# Thermokoppel.net
KiCad netlist of a schematic drawn in Altium Designer
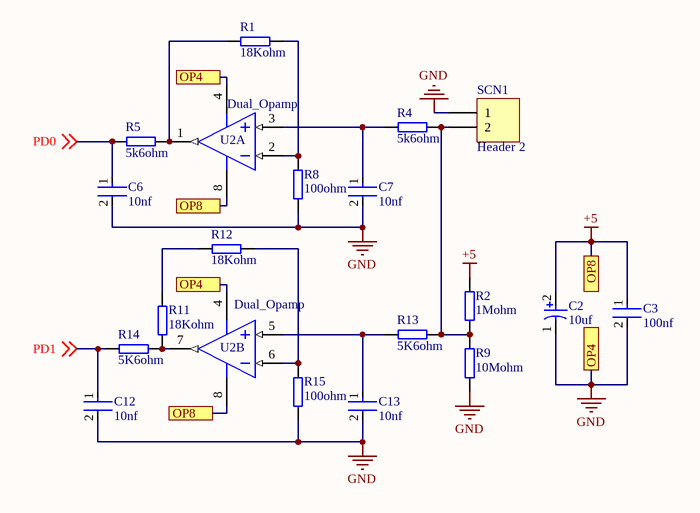
[diagram p0: Thermokoppel.SchDoc]

(export (version "E")
  (design (tool "Eeschema 10.0.6"))
  (components
    (comp (ref "C2")
      (value "10uf")
      (footprint "CE_D4_L5,4")
      (fields (field (name "MANUFACTURER") "Panasonic"))
      (libsource (lib "Soldeerstation_Final") (part "Capacitor_Electrolytic"))
    )
    (comp (ref "C3")
      (value "100nf")
      (footprint "CC_0805_m")
      (fields
        (field (name "MANUFACTURER") "KEMET")
        (field (name "OCTOPART") "https://octopart.com/c0805c224k5ractu-kemet-144670")
        (field (name "MANUFACTURER PART NUMBER") "C0805C224K5RACTU")
      )
      (libsource (lib "Soldeerstation_Final") (part "Capacitor_Ceramic"))
    )
    (comp (ref "C6")
      (value "10nf")
      (footprint "CC_0805_m")
      (fields
        (field (name "MANUFACTURER") "KEMET")
        (field (name "OCTOPART") "https://octopart.com/c0805c224k5ractu-kemet-144670")
        (field (name "MANUFACTURER PART NUMBER") "C0805C224K5RACTU")
      )
      (libsource (lib "Soldeerstation_Final") (part "Capacitor_Ceramic"))
    )
    (comp (ref "C7")
      (value "10nf")
      (footprint "CC_0805_m")
      (fields
        (field (name "MANUFACTURER") "KEMET")
        (field (name "OCTOPART") "https://octopart.com/c0805c224k5ractu-kemet-144670")
        (field (name "MANUFACTURER PART NUMBER") "C0805C224K5RACTU")
      )
      (libsource (lib "Soldeerstation_Final") (part "Capacitor_Ceramic"))
    )
    (comp (ref "C12")
      (value "10nf")
      (footprint "CC_0805_m")
      (fields
        (field (name "MANUFACTURER") "KEMET")
        (field (name "OCTOPART") "https://octopart.com/c0805c224k5ractu-kemet-144670")
        (field (name "MANUFACTURER PART NUMBER") "C0805C224K5RACTU")
      )
      (libsource (lib "Soldeerstation_Final") (part "Capacitor_Ceramic"))
    )
    (comp (ref "C13")
      (value "10nf")
      (footprint "CC_0805_m")
      (fields
        (field (name "MANUFACTURER") "KEMET")
        (field (name "OCTOPART") "https://octopart.com/c0805c224k5ractu-kemet-144670")
        (field (name "MANUFACTURER PART NUMBER") "C0805C224K5RACTU")
      )
      (libsource (lib "Soldeerstation_Final") (part "Capacitor_Ceramic"))
    )
    (comp (ref "R1")
      (value "18Kohm")
      (footprint "R_0805_M")
      (fields (field (name "MANUFACTURER") "Vishay Dale") (field (name "PART NUMBER") "CRCW08050000Z0EA"))
      (libsource (lib "Soldeerstation_Final") (part "Resistor"))
    )
    (comp (ref "R2")
      (value "1Mohm")
      (footprint "R_0805_M")
      (fields (field (name "MANUFACTURER") "Vishay Dale") (field (name "PART NUMBER") "CRCW08050000Z0EA"))
      (libsource (lib "Soldeerstation_Final") (part "Resistor"))
    )
    (comp (ref "R4")
      (value "5k6ohm")
      (footprint "R_0805_M")
      (fields (field (name "MANUFACTURER") "Vishay Dale") (field (name "PART NUMBER") "CRCW08050000Z0EA"))
      (libsource (lib "Soldeerstation_Final") (part "Resistor"))
    )
    (comp (ref "R5")
      (value "5k6ohm")
      (footprint "R_0805_M")
      (fields (field (name "MANUFACTURER") "Vishay Dale") (field (name "PART NUMBER") "CRCW08050000Z0EA"))
      (libsource (lib "Soldeerstation_Final") (part "Resistor"))
    )
    (comp (ref "R8")
      (value "100ohm")
      (footprint "R_0805_M")
      (fields (field (name "MANUFACTURER") "Vishay Dale") (field (name "PART NUMBER") "CRCW08050000Z0EA"))
      (libsource (lib "Soldeerstation_Final") (part "Resistor"))
    )
    (comp (ref "R9")
      (value "10Mohm")
      (footprint "R_0805_M")
      (fields (field (name "MANUFACTURER") "Vishay Dale") (field (name "PART NUMBER") "CRCW08050000Z0EA"))
      (libsource (lib "Soldeerstation_Final") (part "Resistor"))
    )
    (comp (ref "R11")
      (value "18Kohm")
      (footprint "R_0805_M")
      (fields (field (name "MANUFACTURER") "Vishay Dale") (field (name "PART NUMBER") "CRCW08050000Z0EA"))
      (libsource (lib "Soldeerstation_Final") (part "Resistor"))
    )
    (comp (ref "R12")
      (value "18Kohm")
      (footprint "R_0805_M")
      (fields (field (name "MANUFACTURER") "Vishay Dale") (field (name "PART NUMBER") "CRCW08050000Z0EA"))
      (libsource (lib "Soldeerstation_Final") (part "Resistor"))
    )
    (comp (ref "R13")
      (value "5K6ohm")
      (footprint "R_0805_M")
      (fields (field (name "MANUFACTURER") "Vishay Dale") (field (name "PART NUMBER") "CRCW08050000Z0EA"))
      (libsource (lib "Soldeerstation_Final") (part "Resistor"))
    )
    (comp (ref "R14")
      (value "5K6ohm")
      (footprint "R_0805_M")
      (fields (field (name "MANUFACTURER") "Vishay Dale") (field (name "PART NUMBER") "CRCW08050000Z0EA"))
      (libsource (lib "Soldeerstation_Final") (part "Resistor"))
    )
    (comp (ref "R15")
      (value "100ohm")
      (footprint "R_0805_M")
      (fields (field (name "MANUFACTURER") "Vishay Dale") (field (name "PART NUMBER") "CRCW08050000Z0EA"))
      (libsource (lib "Soldeerstation_Final") (part "Resistor"))
    )
    (comp (ref "SCN1")
      (value "Header 2")
      (footprint "Connector_2x1_p_5mm")
      (description "ScrewConnector, 2-Pin")
      (fields (field (name "PUBLISHER") "Altium Limited"))
      (libsource (lib "Miscellaneous Connectors") (part "Header 2"))
    )
    (comp (ref "U2")
      (value "Dual_Opamp")
      (footprint "MSOP_8_M")
      (libsource (lib "Soldeerstation_Final") (part "Dual_Opamp"))
    )
  )
  (nets
    (net (code "1") (name "+5") (class "Default")
      (node (ref "C2") (pin "2") (pinfunction "2_2") (pintype "passive"))
      (node (ref "C3") (pin "1") (pinfunction "1_1") (pintype "passive"))
      (node (ref "R2") (pin "2") (pinfunction "2_2") (pintype "passive"))
      (node (ref "U2") (pin "8") (pinfunction "VDD_8") (pintype "power_in"))
    )
    (net (code "2") (name "GND") (class "Default")
      (node (ref "C12") (pin "2") (pinfunction "2_2") (pintype "passive"))
      (node (ref "C13") (pin "2") (pinfunction "2_2") (pintype "passive"))
      (node (ref "C2") (pin "1") (pinfunction "1_1") (pintype "passive"))
      (node (ref "C3") (pin "2") (pinfunction "2_2") (pintype "passive"))
      (node (ref "C6") (pin "2") (pinfunction "2_2") (pintype "passive"))
      (node (ref "C7") (pin "2") (pinfunction "2_2") (pintype "passive"))
      (node (ref "R15") (pin "1") (pinfunction "1_1") (pintype "passive"))
      (node (ref "R8") (pin "1") (pinfunction "1_1") (pintype "passive"))
      (node (ref "R9") (pin "1") (pinfunction "1_1") (pintype "passive"))
      (node (ref "SCN1") (pin "1") (pinfunction "1_1") (pintype "passive"))
      (node (ref "U2") (pin "4") (pinfunction "VSS_4") (pintype "power_in"))
    )
    (net (code "3") (name "Net-(R11-Pad2)") (class "Default")
      (node (ref "R11") (pin "2") (pinfunction "2_2") (pintype "passive"))
      (node (ref "R12") (pin "1") (pinfunction "1_1") (pintype "passive"))
    )
    (net (code "4") (name "Net-(R13-Pad2)") (class "Default")
      (node (ref "R13") (pin "2") (pinfunction "2_2") (pintype "passive"))
      (node (ref "R2") (pin "1") (pinfunction "1_1") (pintype "passive"))
      (node (ref "R4") (pin "2") (pinfunction "2_2") (pintype "passive"))
      (node (ref "R9") (pin "2") (pinfunction "2_2") (pintype "passive"))
      (node (ref "SCN1") (pin "2") (pinfunction "2_2") (pintype "passive"))
    )
    (net (code "5") (name "Net-(U2A-VINA+)") (class "Default")
      (node (ref "C7") (pin "1") (pinfunction "1_1") (pintype "passive"))
      (node (ref "R4") (pin "1") (pinfunction "1_1") (pintype "passive"))
      (node (ref "U2") (pin "3") (pinfunction "VINA+_3") (pintype "input"))
    )
    (net (code "6") (name "Net-(U2A-VINA-)") (class "Default")
      (node (ref "R1") (pin "2") (pinfunction "2_2") (pintype "passive"))
      (node (ref "R8") (pin "2") (pinfunction "2_2") (pintype "passive"))
      (node (ref "U2") (pin "2") (pinfunction "VINA-_2") (pintype "input"))
    )
    (net (code "7") (name "Net-(U2A-VOUTA)") (class "Default")
      (node (ref "R1") (pin "1") (pinfunction "1_1") (pintype "passive"))
      (node (ref "R5") (pin "2") (pinfunction "2_2") (pintype "passive"))
      (node (ref "U2") (pin "1") (pinfunction "VOUTA_1") (pintype "output"))
    )
    (net (code "8") (name "Net-(U2B-VINB+)") (class "Default")
      (node (ref "C13") (pin "1") (pinfunction "1_1") (pintype "passive"))
      (node (ref "R13") (pin "1") (pinfunction "1_1") (pintype "passive"))
      (node (ref "U2") (pin "5") (pinfunction "VINB+_5") (pintype "input"))
    )
    (net (code "9") (name "Net-(U2B-VINB-)") (class "Default")
      (node (ref "R12") (pin "2") (pinfunction "2_2") (pintype "passive"))
      (node (ref "R15") (pin "2") (pinfunction "2_2") (pintype "passive"))
      (node (ref "U2") (pin "6") (pinfunction "VINB-_6") (pintype "input"))
    )
    (net (code "10") (name "Net-(U2B-VOUTB)") (class "Default")
      (node (ref "R11") (pin "1") (pinfunction "1_1") (pintype "passive"))
      (node (ref "R14") (pin "2") (pinfunction "2_2") (pintype "passive"))
      (node (ref "U2") (pin "7") (pinfunction "VOUTB_7") (pintype "output"))
    )
    (net (code "11") (name "PD0") (class "Default")
      (node (ref "C6") (pin "1") (pinfunction "1_1") (pintype "passive"))
      (node (ref "R5") (pin "1") (pinfunction "1_1") (pintype "passive"))
    )
    (net (code "12") (name "PD1") (class "Default")
      (node (ref "C12") (pin "1") (pinfunction "1_1") (pintype "passive"))
      (node (ref "R14") (pin "1") (pinfunction "1_1") (pintype "passive"))
    )
  )
)
